# Display-Board_Rack-PDU.net
KiCad netlist of a schematic drawn in EAGLE
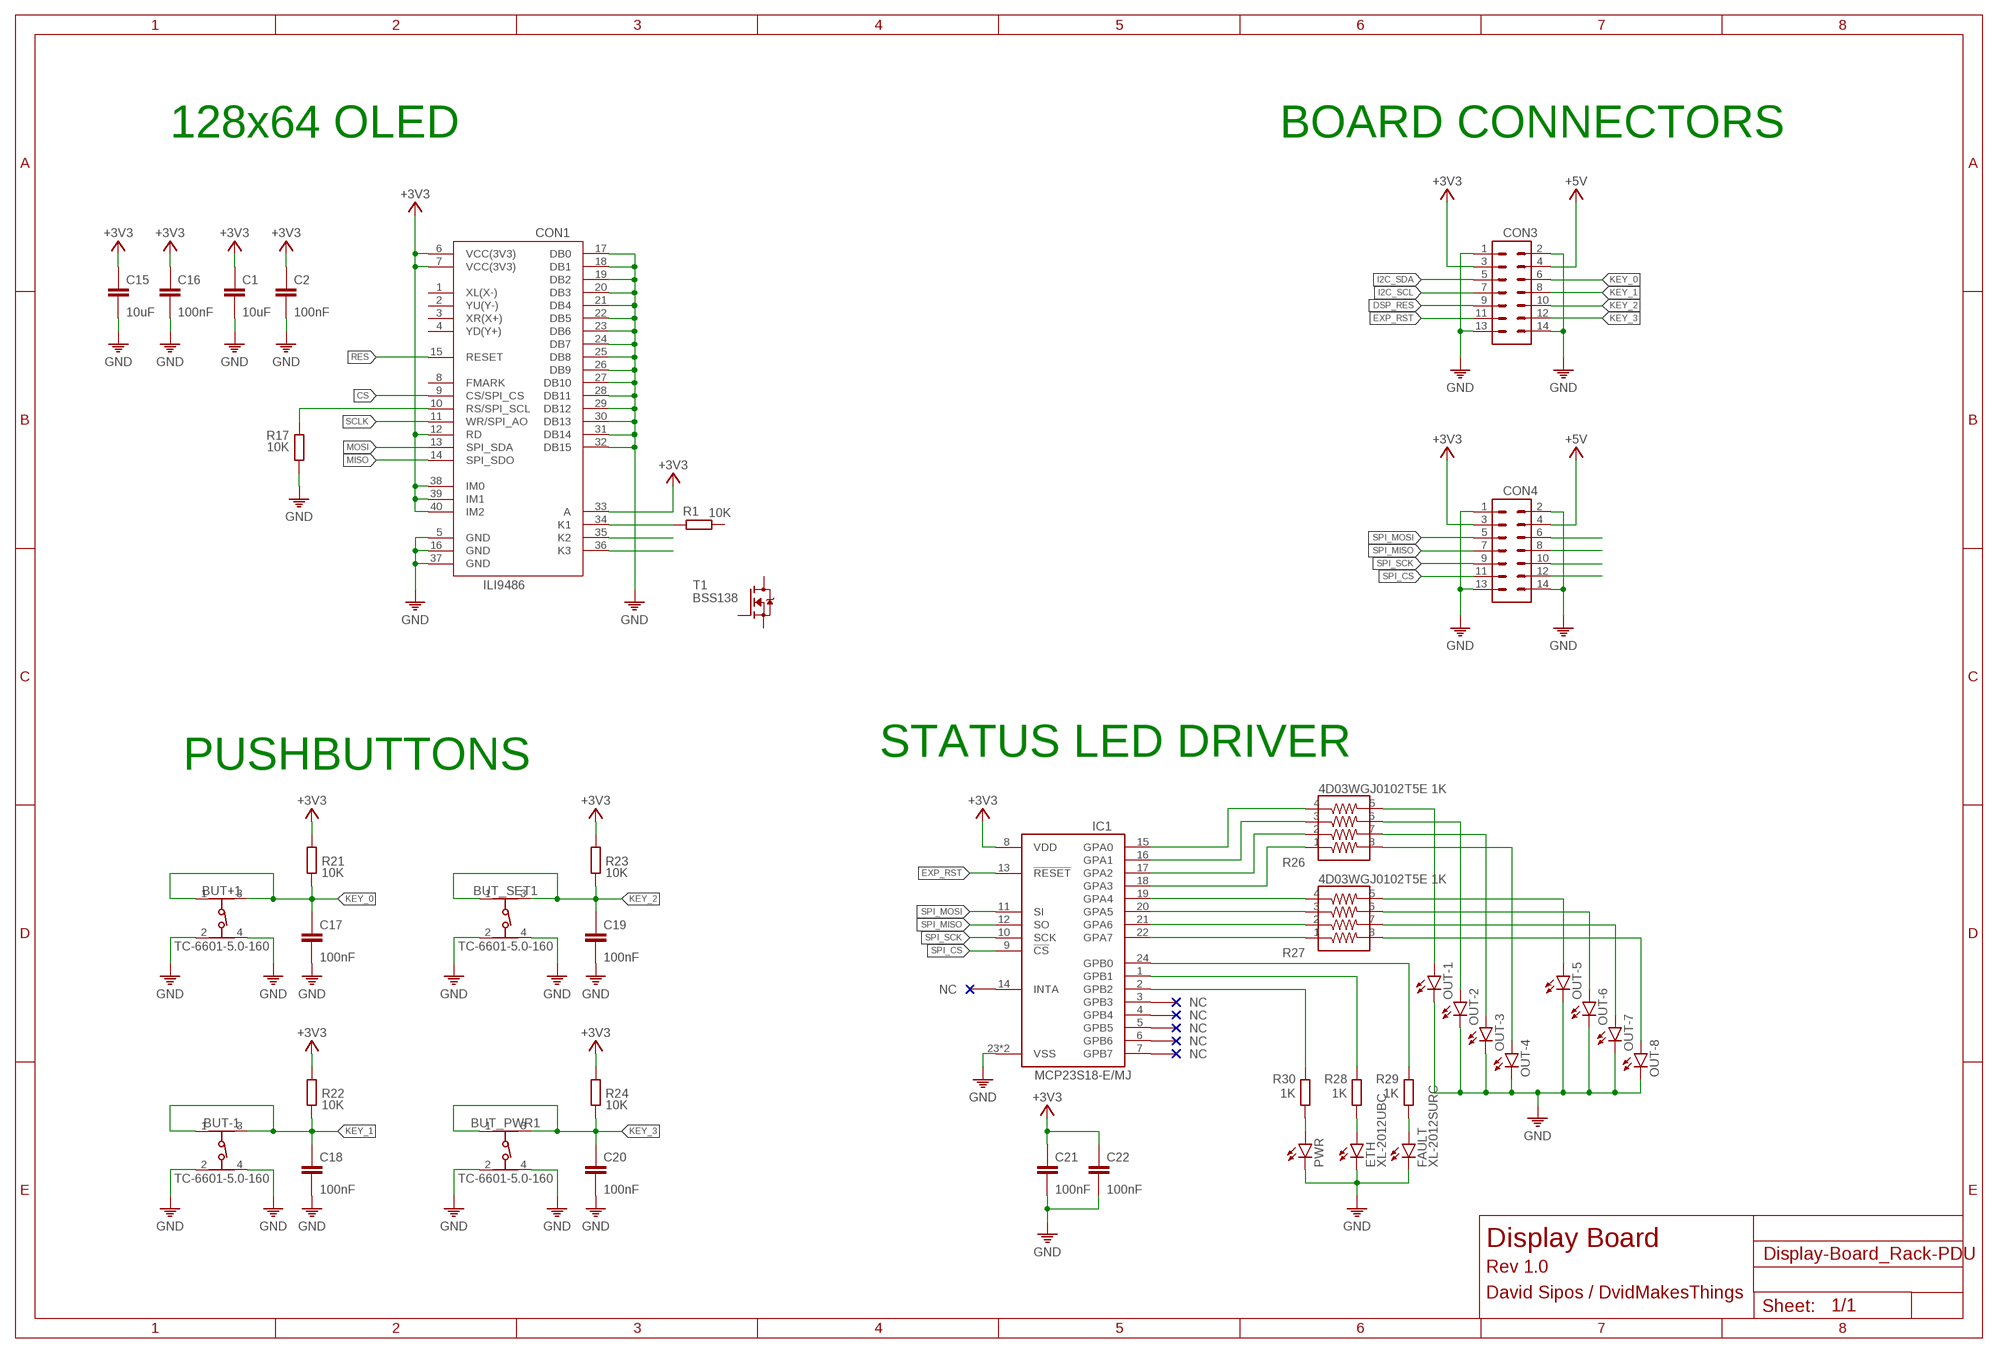
[diagram p0: schematic, sheet 1]

(export (version "E")
  (design (tool "Eeschema 10.0.6"))
  (components
    (comp (ref "BUT+1")
      (value "TC-6601-5.0-160")
      (footprint "eagle-import:430182043816")
      (libsource (lib "eagle-import") (part "430182043816"))
    )
    (comp (ref "BUT-1")
      (value "TC-6601-5.0-160")
      (footprint "eagle-import:430182043816")
      (libsource (lib "eagle-import") (part "430182043816"))
    )
    (comp (ref "BUT_PWR1")
      (value "TC-6601-5.0-160")
      (footprint "eagle-import:430182043816")
      (libsource (lib "eagle-import") (part "430182043816"))
    )
    (comp (ref "BUT_SET1")
      (value "TC-6601-5.0-160")
      (footprint "eagle-import:430182043816")
      (libsource (lib "eagle-import") (part "430182043816"))
    )
    (comp (ref "C1")
      (value "10uF")
      (footprint "eagle-import:C0402")
      (libsource (lib "eagle-import") (part "C-0402"))
    )
    (comp (ref "C2")
      (value "100nF")
      (footprint "eagle-import:C0402")
      (libsource (lib "eagle-import") (part "C-0402"))
    )
    (comp (ref "C15")
      (value "10uF")
      (footprint "eagle-import:C0402")
      (libsource (lib "eagle-import") (part "C-0402"))
    )
    (comp (ref "C16")
      (value "100nF")
      (footprint "eagle-import:C0402")
      (libsource (lib "eagle-import") (part "C-0402"))
    )
    (comp (ref "C17")
      (value "100nF")
      (footprint "eagle-import:C0402")
      (libsource (lib "eagle-import") (part "C-0402"))
    )
    (comp (ref "C18")
      (value "100nF")
      (footprint "eagle-import:C0402")
      (libsource (lib "eagle-import") (part "C-0402"))
    )
    (comp (ref "C19")
      (value "100nF")
      (footprint "eagle-import:C0402")
      (libsource (lib "eagle-import") (part "C-0402"))
    )
    (comp (ref "C20")
      (value "100nF")
      (footprint "eagle-import:C0402")
      (libsource (lib "eagle-import") (part "C-0402"))
    )
    (comp (ref "C21")
      (value "100nF")
      (footprint "eagle-import:C0402")
      (libsource (lib "eagle-import") (part "C-0402"))
    )
    (comp (ref "C22")
      (value "100nF")
      (footprint "eagle-import:C0402")
      (libsource (lib "eagle-import") (part "C-0402"))
    )
    (comp (ref "CON1")
      (value "3.5IN_TFTLCD")
      (footprint "eagle-import:FPC40")
      (libsource (lib "eagle-import") (part "3.5IN_TFTLCD"))
    )
    (comp (ref "CON3")
      (value "CON-2X72")
      (footprint "eagle-import:2X7-SIDE")
      (libsource (lib "eagle-import") (part "CON-2X72"))
    )
    (comp (ref "CON4")
      (value "CON-2X72")
      (footprint "eagle-import:2X7-SIDE")
      (libsource (lib "eagle-import") (part "CON-2X72"))
    )
    (comp (ref "ETH")
      (value "XL-2012UBC")
      (footprint "eagle-import:CHIP-LED0805")
      (libsource (lib "eagle-import") (part "LEDCHIP-LED0805"))
    )
    (comp (ref "FAULT")
      (value "XL-2012SURC")
      (footprint "eagle-import:CHIP-LED0805")
      (libsource (lib "eagle-import") (part "LEDCHIP-LED0805"))
    )
    (comp (ref "IC1")
      (value "MCP23S18-E/MJ")
      (footprint "eagle-import:QFN50P400X400X100-25T265")
      (libsource (lib "eagle-import") (part "MCP23S18"))
    )
    (comp (ref "OUT-1")
      (value "LEDCHIP-LED0805")
      (footprint "eagle-import:CHIP-LED0805")
      (libsource (lib "eagle-import") (part "LEDCHIP-LED0805"))
    )
    (comp (ref "OUT-2")
      (value "LEDCHIP-LED0805")
      (footprint "eagle-import:CHIP-LED0805")
      (libsource (lib "eagle-import") (part "LEDCHIP-LED0805"))
    )
    (comp (ref "OUT-3")
      (value "LEDCHIP-LED0805")
      (footprint "eagle-import:CHIP-LED0805")
      (libsource (lib "eagle-import") (part "LEDCHIP-LED0805"))
    )
    (comp (ref "OUT-4")
      (value "LEDCHIP-LED0805")
      (footprint "eagle-import:CHIP-LED0805")
      (libsource (lib "eagle-import") (part "LEDCHIP-LED0805"))
    )
    (comp (ref "OUT-5")
      (value "LEDCHIP-LED0805")
      (footprint "eagle-import:CHIP-LED0805")
      (libsource (lib "eagle-import") (part "LEDCHIP-LED0805"))
    )
    (comp (ref "OUT-6")
      (value "LEDCHIP-LED0805")
      (footprint "eagle-import:CHIP-LED0805")
      (libsource (lib "eagle-import") (part "LEDCHIP-LED0805"))
    )
    (comp (ref "OUT-7")
      (value "LEDCHIP-LED0805")
      (footprint "eagle-import:CHIP-LED0805")
      (libsource (lib "eagle-import") (part "LEDCHIP-LED0805"))
    )
    (comp (ref "OUT-8")
      (value "LEDCHIP-LED0805")
      (footprint "eagle-import:CHIP-LED0805")
      (libsource (lib "eagle-import") (part "LEDCHIP-LED0805"))
    )
    (comp (ref "PWR")
      (value "LEDCHIP-LED0805")
      (footprint "eagle-import:CHIP-LED0805")
      (libsource (lib "eagle-import") (part "LEDCHIP-LED0805"))
    )
    (comp (ref "R1")
      (value "10K")
      (footprint "eagle-import:0402")
      (libsource (lib "eagle-import") (part "R0402"))
    )
    (comp (ref "R17")
      (value "10K")
      (footprint "eagle-import:0402")
      (libsource (lib "eagle-import") (part "R0402"))
    )
    (comp (ref "R21")
      (value "10K")
      (footprint "eagle-import:0402")
      (libsource (lib "eagle-import") (part "R0402"))
    )
    (comp (ref "R22")
      (value "10K")
      (footprint "eagle-import:0402")
      (libsource (lib "eagle-import") (part "R0402"))
    )
    (comp (ref "R23")
      (value "10K")
      (footprint "eagle-import:0402")
      (libsource (lib "eagle-import") (part "R0402"))
    )
    (comp (ref "R24")
      (value "10K")
      (footprint "eagle-import:0402")
      (libsource (lib "eagle-import") (part "R0402"))
    )
    (comp (ref "R26")
      (value "4D03WGJ0102T5E 1K")
      (footprint "eagle-import:742C083103JP")
      (fields
        (field (name "MANUFACTURER") "CTS Resistor Products")
        (field (name "MPN") "742C083103JP")
        (field (name "CREATED_BY") "PCBLayout.com")
      )
      (libsource (lib "eagle-import") (part "742C083103JP"))
    )
    (comp (ref "R27")
      (value "4D03WGJ0102T5E 1K")
      (footprint "eagle-import:742C083103JP")
      (fields
        (field (name "MANUFACTURER") "CTS Resistor Products")
        (field (name "MPN") "742C083103JP")
        (field (name "CREATED_BY") "PCBLayout.com")
      )
      (libsource (lib "eagle-import") (part "742C083103JP"))
    )
    (comp (ref "R28")
      (value "1K")
      (footprint "eagle-import:0402")
      (libsource (lib "eagle-import") (part "R0402"))
    )
    (comp (ref "R29")
      (value "1K")
      (footprint "eagle-import:0402")
      (libsource (lib "eagle-import") (part "R0402"))
    )
    (comp (ref "R30")
      (value "1K")
      (footprint "eagle-import:0402")
      (libsource (lib "eagle-import") (part "R0402"))
    )
    (comp (ref "T1")
      (value "BSS138")
      (footprint "eagle-import:SOT23")
      (libsource (lib "eagle-import") (part "BSS138"))
    )
  )
  (nets
    (net (code "1") (name "+3V3") (class "Default")
      (node (ref "C1") (pin "1") (pinfunction "1_1") (pintype "passive"))
      (node (ref "C15") (pin "1") (pinfunction "1_1") (pintype "passive"))
      (node (ref "C16") (pin "1") (pinfunction "1_1") (pintype "passive"))
      (node (ref "C2") (pin "1") (pinfunction "1_1") (pintype "passive"))
      (node (ref "C21") (pin "1") (pinfunction "1_1") (pintype "passive"))
      (node (ref "C22") (pin "1") (pinfunction "1_1") (pintype "passive"))
      (node (ref "CON1") (pin "12") (pinfunction "RD_12") (pintype "bidirectional"))
      (node (ref "CON1") (pin "33") (pinfunction "A_33") (pintype "bidirectional"))
      (node (ref "CON1") (pin "38") (pinfunction "IM0_38") (pintype "bidirectional"))
      (node (ref "CON1") (pin "39") (pinfunction "IM1_39") (pintype "bidirectional"))
      (node (ref "CON1") (pin "40") (pinfunction "IM2_40") (pintype "bidirectional"))
      (node (ref "CON1") (pin "6") (pinfunction "VCC(3V3)_6") (pintype "bidirectional"))
      (node (ref "CON1") (pin "7") (pinfunction "VCC(3V3)_7") (pintype "bidirectional"))
      (node (ref "CON3") (pin "3") (pinfunction "3_3") (pintype "bidirectional"))
      (node (ref "CON4") (pin "3") (pinfunction "3_3") (pintype "bidirectional"))
      (node (ref "IC1") (pin "8") (pinfunction "VDD_8") (pintype "power_in"))
      (node (ref "R21") (pin "1") (pinfunction "1_1") (pintype "passive"))
      (node (ref "R22") (pin "1") (pinfunction "1_1") (pintype "passive"))
      (node (ref "R23") (pin "1") (pinfunction "1_1") (pintype "passive"))
      (node (ref "R24") (pin "1") (pinfunction "1_1") (pintype "passive"))
    )
    (net (code "2") (name "+5V") (class "Default")
      (node (ref "CON3") (pin "4") (pinfunction "4_4") (pintype "bidirectional"))
      (node (ref "CON4") (pin "4") (pinfunction "4_4") (pintype "bidirectional"))
    )
    (net (code "3") (name "CS") (class "Default")
      (node (ref "CON1") (pin "9") (pinfunction "CS/SPI_CS_9") (pintype "bidirectional"))
    )
    (net (code "4") (name "DSP_RES") (class "Default")
      (node (ref "CON3") (pin "9") (pinfunction "9_9") (pintype "bidirectional"))
    )
    (net (code "5") (name "EXP_RST") (class "Default")
      (node (ref "CON3") (pin "11") (pinfunction "11_11") (pintype "bidirectional"))
      (node (ref "IC1") (pin "13") (pinfunction "~{RESET}_13") (pintype "input"))
    )
    (net (code "6") (name "GND") (class "Default")
      (node (ref "BUT+1") (pin "2") (pinfunction "2_2") (pintype "passive"))
      (node (ref "BUT+1") (pin "4") (pinfunction "4_4") (pintype "passive"))
      (node (ref "BUT-1") (pin "2") (pinfunction "2_2") (pintype "passive"))
      (node (ref "BUT-1") (pin "4") (pinfunction "4_4") (pintype "passive"))
      (node (ref "BUT_PWR1") (pin "2") (pinfunction "2_2") (pintype "passive"))
      (node (ref "BUT_PWR1") (pin "4") (pinfunction "4_4") (pintype "passive"))
      (node (ref "BUT_SET1") (pin "2") (pinfunction "2_2") (pintype "passive"))
      (node (ref "BUT_SET1") (pin "4") (pinfunction "4_4") (pintype "passive"))
      (node (ref "C1") (pin "2") (pinfunction "2_2") (pintype "passive"))
      (node (ref "C15") (pin "2") (pinfunction "2_2") (pintype "passive"))
      (node (ref "C16") (pin "2") (pinfunction "2_2") (pintype "passive"))
      (node (ref "C17") (pin "2") (pinfunction "2_2") (pintype "passive"))
      (node (ref "C18") (pin "2") (pinfunction "2_2") (pintype "passive"))
      (node (ref "C19") (pin "2") (pinfunction "2_2") (pintype "passive"))
      (node (ref "C2") (pin "2") (pinfunction "2_2") (pintype "passive"))
      (node (ref "C20") (pin "2") (pinfunction "2_2") (pintype "passive"))
      (node (ref "C21") (pin "2") (pinfunction "2_2") (pintype "passive"))
      (node (ref "C22") (pin "2") (pinfunction "2_2") (pintype "passive"))
      (node (ref "CON1") (pin "16") (pinfunction "GND_16") (pintype "bidirectional"))
      (node (ref "CON1") (pin "17") (pinfunction "DB0_17") (pintype "bidirectional"))
      (node (ref "CON1") (pin "18") (pinfunction "DB1_18") (pintype "bidirectional"))
      (node (ref "CON1") (pin "19") (pinfunction "DB2_19") (pintype "bidirectional"))
      (node (ref "CON1") (pin "20") (pinfunction "DB3_20") (pintype "bidirectional"))
      (node (ref "CON1") (pin "21") (pinfunction "DB4_21") (pintype "bidirectional"))
      (node (ref "CON1") (pin "22") (pinfunction "DB5_22") (pintype "bidirectional"))
      (node (ref "CON1") (pin "23") (pinfunction "DB6_23") (pintype "bidirectional"))
      (node (ref "CON1") (pin "24") (pinfunction "DB7_24") (pintype "bidirectional"))
      (node (ref "CON1") (pin "25") (pinfunction "DB8_25") (pintype "bidirectional"))
      (node (ref "CON1") (pin "26") (pinfunction "DB9_26") (pintype "bidirectional"))
      (node (ref "CON1") (pin "27") (pinfunction "DB10_27") (pintype "bidirectional"))
      (node (ref "CON1") (pin "28") (pinfunction "DB11_28") (pintype "bidirectional"))
      (node (ref "CON1") (pin "29") (pinfunction "DB12_29") (pintype "bidirectional"))
      (node (ref "CON1") (pin "30") (pinfunction "DB13_30") (pintype "bidirectional"))
      (node (ref "CON1") (pin "31") (pinfunction "DB14_31") (pintype "bidirectional"))
      (node (ref "CON1") (pin "32") (pinfunction "DB15_32") (pintype "bidirectional"))
      (node (ref "CON1") (pin "37") (pinfunction "GND_37") (pintype "bidirectional"))
      (node (ref "CON1") (pin "5") (pinfunction "GND_5") (pintype "bidirectional"))
      (node (ref "CON3") (pin "1") (pinfunction "1_1") (pintype "bidirectional"))
      (node (ref "CON3") (pin "13") (pinfunction "13_13") (pintype "bidirectional"))
      (node (ref "CON3") (pin "14") (pinfunction "14_14") (pintype "bidirectional"))
      (node (ref "CON3") (pin "2") (pinfunction "2_2") (pintype "bidirectional"))
      (node (ref "CON4") (pin "1") (pinfunction "1_1") (pintype "bidirectional"))
      (node (ref "CON4") (pin "13") (pinfunction "13_13") (pintype "bidirectional"))
      (node (ref "CON4") (pin "14") (pinfunction "14_14") (pintype "bidirectional"))
      (node (ref "CON4") (pin "2") (pinfunction "2_2") (pintype "bidirectional"))
      (node (ref "ETH") (pin "C") (pinfunction "C_C") (pintype "passive"))
      (node (ref "FAULT") (pin "C") (pinfunction "C_C") (pintype "passive"))
      (node (ref "IC1") (pin "23") (pinfunction "VSS_23") (pintype "power_in"))
      (node (ref "IC1") (pin "25") (pinfunction "VSS_25") (pintype "power_in"))
      (node (ref "OUT-1") (pin "C") (pinfunction "C_C") (pintype "passive"))
      (node (ref "OUT-2") (pin "C") (pinfunction "C_C") (pintype "passive"))
      (node (ref "OUT-3") (pin "C") (pinfunction "C_C") (pintype "passive"))
      (node (ref "OUT-4") (pin "C") (pinfunction "C_C") (pintype "passive"))
      (node (ref "OUT-5") (pin "C") (pinfunction "C_C") (pintype "passive"))
      (node (ref "OUT-6") (pin "C") (pinfunction "C_C") (pintype "passive"))
      (node (ref "OUT-7") (pin "C") (pinfunction "C_C") (pintype "passive"))
      (node (ref "OUT-8") (pin "C") (pinfunction "C_C") (pintype "passive"))
      (node (ref "PWR") (pin "C") (pinfunction "C_C") (pintype "passive"))
      (node (ref "R17") (pin "1") (pinfunction "1_1") (pintype "passive"))
    )
    (net (code "7") (name "I2C_SCL") (class "Default")
      (node (ref "CON3") (pin "7") (pinfunction "7_7") (pintype "bidirectional"))
    )
    (net (code "8") (name "I2C_SDA") (class "Default")
      (node (ref "CON3") (pin "5") (pinfunction "5_5") (pintype "bidirectional"))
    )
    (net (code "9") (name "KEY_0") (class "Default")
      (node (ref "BUT+1") (pin "1") (pinfunction "1_1") (pintype "passive"))
      (node (ref "BUT+1") (pin "3") (pinfunction "3_3") (pintype "passive"))
      (node (ref "C17") (pin "1") (pinfunction "1_1") (pintype "passive"))
      (node (ref "CON3") (pin "6") (pinfunction "6_6") (pintype "bidirectional"))
      (node (ref "R21") (pin "2") (pinfunction "2_2") (pintype "passive"))
    )
    (net (code "10") (name "KEY_1") (class "Default")
      (node (ref "BUT-1") (pin "1") (pinfunction "1_1") (pintype "passive"))
      (node (ref "BUT-1") (pin "3") (pinfunction "3_3") (pintype "passive"))
      (node (ref "C18") (pin "1") (pinfunction "1_1") (pintype "passive"))
      (node (ref "CON3") (pin "8") (pinfunction "8_8") (pintype "bidirectional"))
      (node (ref "R22") (pin "2") (pinfunction "2_2") (pintype "passive"))
    )
    (net (code "11") (name "KEY_2") (class "Default")
      (node (ref "BUT_SET1") (pin "1") (pinfunction "1_1") (pintype "passive"))
      (node (ref "BUT_SET1") (pin "3") (pinfunction "3_3") (pintype "passive"))
      (node (ref "C19") (pin "1") (pinfunction "1_1") (pintype "passive"))
      (node (ref "CON3") (pin "10") (pinfunction "10_10") (pintype "bidirectional"))
      (node (ref "R23") (pin "2") (pinfunction "2_2") (pintype "passive"))
    )
    (net (code "12") (name "KEY_3") (class "Default")
      (node (ref "BUT_PWR1") (pin "1") (pinfunction "1_1") (pintype "passive"))
      (node (ref "BUT_PWR1") (pin "3") (pinfunction "3_3") (pintype "passive"))
      (node (ref "C20") (pin "1") (pinfunction "1_1") (pintype "passive"))
      (node (ref "CON3") (pin "12") (pinfunction "12_12") (pintype "bidirectional"))
      (node (ref "R24") (pin "2") (pinfunction "2_2") (pintype "passive"))
    )
    (net (code "13") (name "MISO") (class "Default")
      (node (ref "CON1") (pin "14") (pinfunction "SPI_SDO_14") (pintype "bidirectional"))
    )
    (net (code "14") (name "MOSI") (class "Default")
      (node (ref "CON1") (pin "13") (pinfunction "SPI_SDA_13") (pintype "bidirectional"))
    )
    (net (code "15") (name "Net-(CON1-K1)") (class "Default")
      (node (ref "CON1") (pin "34") (pinfunction "K1_34") (pintype "bidirectional"))
      (node (ref "R1") (pin "2") (pinfunction "2_2") (pintype "passive"))
    )
    (net (code "16") (name "Net-(CON1-RS{slash}SPI_SCL)") (class "Default")
      (node (ref "CON1") (pin "10") (pinfunction "RS/SPI_SCL_10") (pintype "bidirectional"))
      (node (ref "R17") (pin "2") (pinfunction "2_2") (pintype "passive"))
    )
    (net (code "17") (name "Net-(ETH-PadA)") (class "Default")
      (node (ref "ETH") (pin "A") (pinfunction "A_A") (pintype "passive"))
      (node (ref "R28") (pin "2") (pinfunction "2_2") (pintype "passive"))
    )
    (net (code "18") (name "Net-(FAULT-PadA)") (class "Default")
      (node (ref "FAULT") (pin "A") (pinfunction "A_A") (pintype "passive"))
      (node (ref "R29") (pin "2") (pinfunction "2_2") (pintype "passive"))
    )
    (net (code "19") (name "Net-(IC1-GPA0)") (class "Default")
      (node (ref "IC1") (pin "15") (pinfunction "GPA0_15") (pintype "bidirectional"))
      (node (ref "R26") (pin "4") (pinfunction "4_4") (pintype "passive"))
    )
    (net (code "20") (name "Net-(IC1-GPA1)") (class "Default")
      (node (ref "IC1") (pin "16") (pinfunction "GPA1_16") (pintype "bidirectional"))
      (node (ref "R26") (pin "3") (pinfunction "3_3") (pintype "passive"))
    )
    (net (code "21") (name "Net-(IC1-GPA2)") (class "Default")
      (node (ref "IC1") (pin "17") (pinfunction "GPA2_17") (pintype "bidirectional"))
      (node (ref "R26") (pin "2") (pinfunction "2_2") (pintype "passive"))
    )
    (net (code "22") (name "Net-(IC1-GPA3)") (class "Default")
      (node (ref "IC1") (pin "18") (pinfunction "GPA3_18") (pintype "bidirectional"))
      (node (ref "R26") (pin "1") (pinfunction "1_1") (pintype "passive"))
    )
    (net (code "23") (name "Net-(IC1-GPA4)") (class "Default")
      (node (ref "IC1") (pin "19") (pinfunction "GPA4_19") (pintype "bidirectional"))
      (node (ref "R27") (pin "4") (pinfunction "4_4") (pintype "passive"))
    )
    (net (code "24") (name "Net-(IC1-GPA5)") (class "Default")
      (node (ref "IC1") (pin "20") (pinfunction "GPA5_20") (pintype "bidirectional"))
      (node (ref "R27") (pin "3") (pinfunction "3_3") (pintype "passive"))
    )
    (net (code "25") (name "Net-(IC1-GPA6)") (class "Default")
      (node (ref "IC1") (pin "21") (pinfunction "GPA6_21") (pintype "bidirectional"))
      (node (ref "R27") (pin "2") (pinfunction "2_2") (pintype "passive"))
    )
    (net (code "26") (name "Net-(IC1-GPA7)") (class "Default")
      (node (ref "IC1") (pin "22") (pinfunction "GPA7_22") (pintype "bidirectional"))
      (node (ref "R27") (pin "1") (pinfunction "1_1") (pintype "passive"))
    )
    (net (code "27") (name "Net-(IC1-GPB0)") (class "Default")
      (node (ref "IC1") (pin "24") (pinfunction "GPB0_24") (pintype "bidirectional"))
      (node (ref "R29") (pin "1") (pinfunction "1_1") (pintype "passive"))
    )
    (net (code "28") (name "Net-(IC1-GPB1)") (class "Default")
      (node (ref "IC1") (pin "1") (pinfunction "GPB1_1") (pintype "bidirectional"))
      (node (ref "R28") (pin "1") (pinfunction "1_1") (pintype "passive"))
    )
    (net (code "29") (name "Net-(IC1-GPB2)") (class "Default")
      (node (ref "IC1") (pin "2") (pinfunction "GPB2_2") (pintype "bidirectional"))
      (node (ref "R30") (pin "1") (pinfunction "1_1") (pintype "passive"))
    )
    (net (code "30") (name "Net-(OUT-1-PadA)") (class "Default")
      (node (ref "OUT-1") (pin "A") (pinfunction "A_A") (pintype "passive"))
      (node (ref "R26") (pin "5") (pinfunction "5_5") (pintype "passive"))
    )
    (net (code "31") (name "Net-(OUT-2-PadA)") (class "Default")
      (node (ref "OUT-2") (pin "A") (pinfunction "A_A") (pintype "passive"))
      (node (ref "R26") (pin "6") (pinfunction "6_6") (pintype "passive"))
    )
    (net (code "32") (name "Net-(OUT-3-PadA)") (class "Default")
      (node (ref "OUT-3") (pin "A") (pinfunction "A_A") (pintype "passive"))
      (node (ref "R26") (pin "7") (pinfunction "7_7") (pintype "passive"))
    )
    (net (code "33") (name "Net-(OUT-4-PadA)") (class "Default")
      (node (ref "OUT-4") (pin "A") (pinfunction "A_A") (pintype "passive"))
      (node (ref "R26") (pin "8") (pinfunction "8_8") (pintype "passive"))
    )
    (net (code "34") (name "Net-(OUT-5-PadA)") (class "Default")
      (node (ref "OUT-5") (pin "A") (pinfunction "A_A") (pintype "passive"))
      (node (ref "R27") (pin "5") (pinfunction "5_5") (pintype "passive"))
    )
    (net (code "35") (name "Net-(OUT-6-PadA)") (class "Default")
      (node (ref "OUT-6") (pin "A") (pinfunction "A_A") (pintype "passive"))
      (node (ref "R27") (pin "6") (pinfunction "6_6") (pintype "passive"))
    )
    (net (code "36") (name "Net-(OUT-7-PadA)") (class "Default")
      (node (ref "OUT-7") (pin "A") (pinfunction "A_A") (pintype "passive"))
      (node (ref "R27") (pin "7") (pinfunction "7_7") (pintype "passive"))
    )
    (net (code "37") (name "Net-(OUT-8-PadA)") (class "Default")
      (node (ref "OUT-8") (pin "A") (pinfunction "A_A") (pintype "passive"))
      (node (ref "R27") (pin "8") (pinfunction "8_8") (pintype "passive"))
    )
    (net (code "38") (name "Net-(PWR-PadA)") (class "Default")
      (node (ref "PWR") (pin "A") (pinfunction "A_A") (pintype "passive"))
      (node (ref "R30") (pin "2") (pinfunction "2_2") (pintype "passive"))
    )
    (net (code "39") (name "RES") (class "Default")
      (node (ref "CON1") (pin "15") (pinfunction "RESET_15") (pintype "bidirectional"))
    )
    (net (code "40") (name "SCLK") (class "Default")
      (node (ref "CON1") (pin "11") (pinfunction "WR/SPI_AO_11") (pintype "bidirectional"))
    )
    (net (code "41") (name "SPI_CS") (class "Default")
      (node (ref "CON4") (pin "11") (pinfunction "11_11") (pintype "bidirectional"))
      (node (ref "IC1") (pin "9") (pinfunction "~{CS}_9") (pintype "input"))
    )
    (net (code "42") (name "SPI_MISO") (class "Default")
      (node (ref "CON4") (pin "7") (pinfunction "7_7") (pintype "bidirectional"))
      (node (ref "IC1") (pin "12") (pinfunction "SO_12") (pintype "output"))
    )
    (net (code "43") (name "SPI_MOSI") (class "Default")
      (node (ref "CON4") (pin "5") (pinfunction "5_5") (pintype "bidirectional"))
      (node (ref "IC1") (pin "11") (pinfunction "SI_11") (pintype "input"))
    )
    (net (code "44") (name "SPI_SCK") (class "Default")
      (node (ref "CON4") (pin "9") (pinfunction "9_9") (pintype "bidirectional"))
      (node (ref "IC1") (pin "10") (pinfunction "SCK_10") (pintype "input"))
    )
    (net (code "45") (name "unconnected-(CON1-FMARK-Pad8)") (class "Default")
      (node (ref "CON1") (pin "8") (pinfunction "FMARK_8") (pintype "bidirectional"))
    )
    (net (code "46") (name "unconnected-(CON1-K2-Pad35)") (class "Default")
      (node (ref "CON1") (pin "35") (pinfunction "K2_35") (pintype "bidirectional"))
    )
    (net (code "47") (name "unconnected-(CON1-K3-Pad36)") (class "Default")
      (node (ref "CON1") (pin "36") (pinfunction "K3_36") (pintype "bidirectional"))
    )
    (net (code "48") (name "unconnected-(CON1-XL(X-)-Pad1)") (class "Default")
      (node (ref "CON1") (pin "1") (pinfunction "XL(X-)_1") (pintype "bidirectional"))
    )
    (net (code "49") (name "unconnected-(CON1-XR(X+)-Pad3)") (class "Default")
      (node (ref "CON1") (pin "3") (pinfunction "XR(X+)_3") (pintype "bidirectional"))
    )
    (net (code "50") (name "unconnected-(CON1-YD(Y+)-Pad4)") (class "Default")
      (node (ref "CON1") (pin "4") (pinfunction "YD(Y+)_4") (pintype "bidirectional"))
    )
    (net (code "51") (name "unconnected-(CON1-YU(Y-)-Pad2)") (class "Default")
      (node (ref "CON1") (pin "2") (pinfunction "YU(Y-)_2") (pintype "bidirectional"))
    )
    (net (code "52") (name "unconnected-(CON4-Pad6)") (class "Default")
      (node (ref "CON4") (pin "6") (pinfunction "6_6") (pintype "bidirectional"))
    )
    (net (code "53") (name "unconnected-(CON4-Pad8)") (class "Default")
      (node (ref "CON4") (pin "8") (pinfunction "8_8") (pintype "bidirectional"))
    )
    (net (code "54") (name "unconnected-(CON4-Pad10)") (class "Default")
      (node (ref "CON4") (pin "10") (pinfunction "10_10") (pintype "bidirectional"))
    )
    (net (code "55") (name "unconnected-(CON4-Pad12)") (class "Default")
      (node (ref "CON4") (pin "12") (pinfunction "12_12") (pintype "bidirectional"))
    )
    (net (code "56") (name "unconnected-(IC1-GPB3-Pad3)") (class "Default")
      (node (ref "IC1") (pin "3") (pinfunction "GPB3_3") (pintype "bidirectional"))
    )
    (net (code "57") (name "unconnected-(IC1-GPB4-Pad4)") (class "Default")
      (node (ref "IC1") (pin "4") (pinfunction "GPB4_4") (pintype "bidirectional"))
    )
    (net (code "58") (name "unconnected-(IC1-GPB5-Pad5)") (class "Default")
      (node (ref "IC1") (pin "5") (pinfunction "GPB5_5") (pintype "bidirectional"))
    )
    (net (code "59") (name "unconnected-(IC1-GPB6-Pad6)") (class "Default")
      (node (ref "IC1") (pin "6") (pinfunction "GPB6_6") (pintype "bidirectional"))
    )
    (net (code "60") (name "unconnected-(IC1-GPB7-Pad7)") (class "Default")
      (node (ref "IC1") (pin "7") (pinfunction "GPB7_7") (pintype "bidirectional"))
    )
    (net (code "61") (name "unconnected-(IC1-INTA-Pad14)") (class "Default")
      (node (ref "IC1") (pin "14") (pinfunction "INTA_14") (pintype "output"))
    )
    (net (code "62") (name "unconnected-(R1-Pad1)") (class "Default")
      (node (ref "R1") (pin "1") (pinfunction "1_1") (pintype "passive"))
    )
    (net (code "63") (name "unconnected-(T1-D-Pad3)") (class "Default")
      (node (ref "T1") (pin "3") (pinfunction "D_3") (pintype "passive"))
    )
    (net (code "64") (name "unconnected-(T1-G-Pad1)") (class "Default")
      (node (ref "T1") (pin "1") (pinfunction "G_1") (pintype "passive"))
    )
    (net (code "65") (name "unconnected-(T1-S-Pad2)") (class "Default")
      (node (ref "T1") (pin "2") (pinfunction "S_2") (pintype "passive"))
    )
  )
)
